# Adafruit_UPDI_Friend.net
KiCad netlist of a schematic drawn in EAGLE
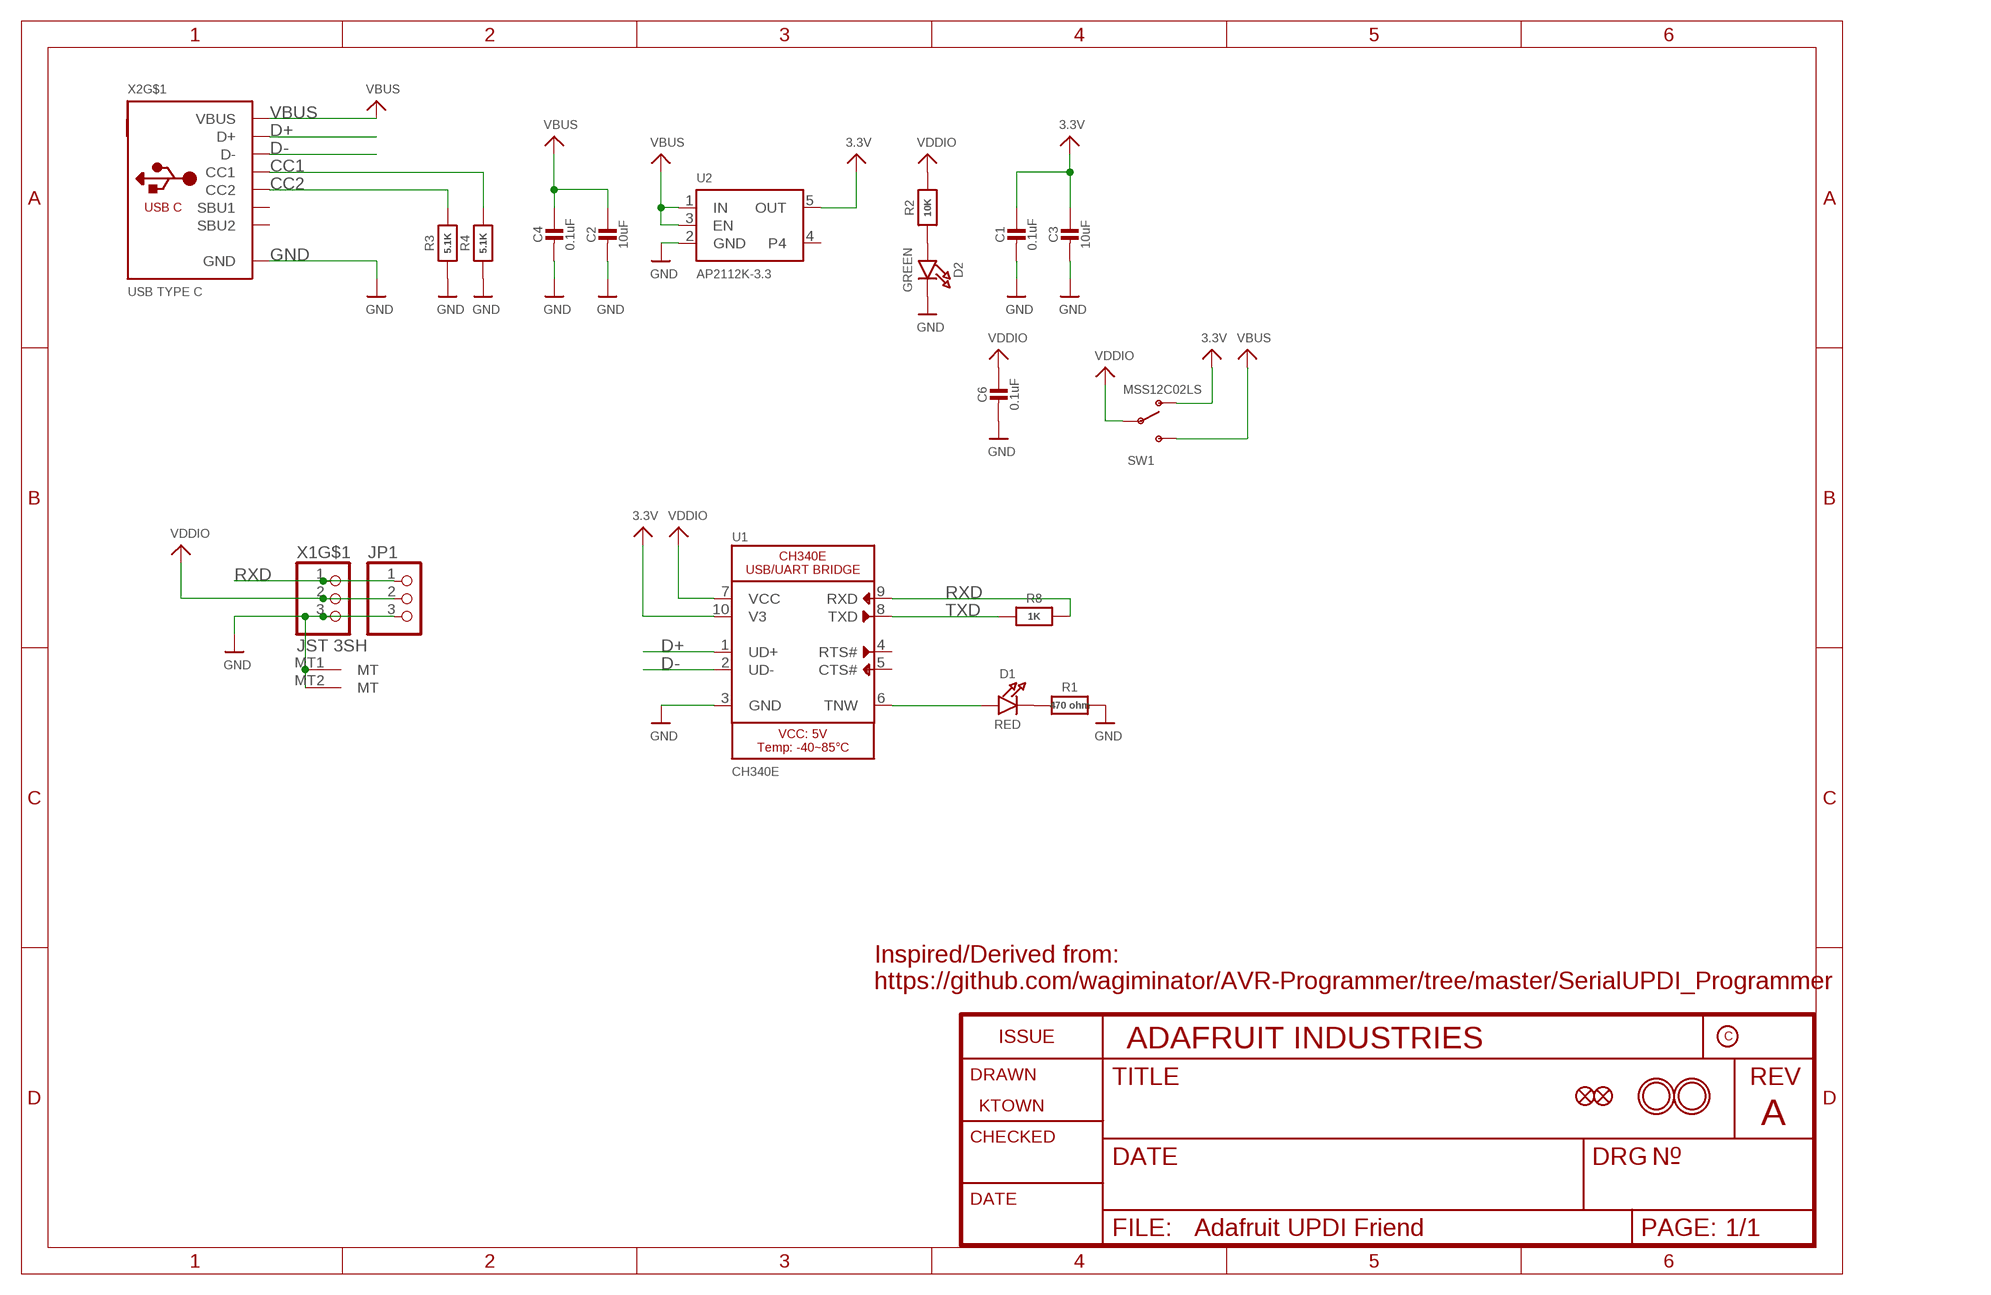
[diagram p0: schematic, sheet 1]

(export (version "E")
  (design (tool "Eeschema 10.0.6"))
  (components
    (comp (ref "C1")
      (value "0.1uF")
      (footprint "eagle-import:0603-NO")
      (libsource (lib "eagle-import") (part "CAP_CERAMIC0603_NO"))
    )
    (comp (ref "C2")
      (value "10uF")
      (footprint "eagle-import:0805-NO")
      (libsource (lib "eagle-import") (part "CAP_CERAMIC0805-NOOUTLINE"))
    )
    (comp (ref "C3")
      (value "10uF")
      (footprint "eagle-import:0805-NO")
      (libsource (lib "eagle-import") (part "CAP_CERAMIC0805-NOOUTLINE"))
    )
    (comp (ref "C4")
      (value "0.1uF")
      (footprint "eagle-import:0603-NO")
      (libsource (lib "eagle-import") (part "CAP_CERAMIC0603_NO"))
    )
    (comp (ref "C6")
      (value "0.1uF")
      (footprint "eagle-import:0603-NO")
      (libsource (lib "eagle-import") (part "CAP_CERAMIC0603_NO"))
    )
    (comp (ref "D1")
      (value "RED")
      (footprint "eagle-import:CHIPLED_0603_NOOUTLINE")
      (libsource (lib "eagle-import") (part "LED0603_NOOUTLINE"))
    )
    (comp (ref "D2")
      (value "GREEN")
      (footprint "eagle-import:CHIPLED_0603_NOOUTLINE")
      (libsource (lib "eagle-import") (part "LED0603_NOOUTLINE"))
    )
    (comp (ref "FID1")
      (value "FIDUCIAL_1MM")
      (footprint "eagle-import:FIDUCIAL_1MM")
      (libsource (lib "eagle-import") (part "FIDUCIAL_1MM"))
    )
    (comp (ref "FID2")
      (value "FIDUCIAL_1MM")
      (footprint "eagle-import:FIDUCIAL_1MM")
      (libsource (lib "eagle-import") (part "FIDUCIAL_1MM"))
    )
    (comp (ref "JP1")
      (value "HEADER-1X376MIL")
      (footprint "eagle-import:1X03_ROUND_76")
      (libsource (lib "eagle-import") (part "HEADER-1X376MIL"))
    )
    (comp (ref "R1")
      (value "470 ohm")
      (footprint "eagle-import:0603-NO")
      (libsource (lib "eagle-import") (part "RESISTOR_0603_NOOUT"))
    )
    (comp (ref "R2")
      (value "10K")
      (footprint "eagle-import:0603-NO")
      (libsource (lib "eagle-import") (part "RESISTOR_0603_NOOUT"))
    )
    (comp (ref "R3")
      (value "5.1K")
      (footprint "eagle-import:0603-NO")
      (libsource (lib "eagle-import") (part "RESISTOR_0603_NOOUT"))
    )
    (comp (ref "R4")
      (value "5.1K")
      (footprint "eagle-import:0603-NO")
      (libsource (lib "eagle-import") (part "RESISTOR_0603_NOOUT"))
    )
    (comp (ref "R8")
      (value "1K")
      (footprint "eagle-import:0603-NO")
      (libsource (lib "eagle-import") (part "RESISTOR_0603_NOOUT"))
    )
    (comp (ref "SW1")
      (value "MSS12C02LS")
      (footprint "eagle-import:SPDT_SMT_SSSS811101")
      (libsource (lib "eagle-import") (part "SWITCH_SPDT"))
    )
    (comp (ref "U$18")
      (value "MOUNTINGHOLE2.0")
      (footprint "eagle-import:MOUNTINGHOLE_2.0_PLATED")
      (libsource (lib "eagle-import") (part "MOUNTINGHOLE2.0"))
    )
    (comp (ref "U$19")
      (value "MOUNTINGHOLE2.0")
      (footprint "eagle-import:MOUNTINGHOLE_2.0_PLATED")
      (libsource (lib "eagle-import") (part "MOUNTINGHOLE2.0"))
    )
    (comp (ref "U1")
      (value "CH340E")
      (footprint "eagle-import:MSOP10")
      (libsource (lib "eagle-import") (part "CH340E_MSOP10"))
    )
    (comp (ref "U2")
      (value "AP2112K-3.3")
      (footprint "eagle-import:SOT23-5")
      (fields (field (name "JLC_ROTATION") "0"))
      (libsource (lib "eagle-import") (part "VREG_SOT23-5"))
    )
    (comp (ref "X1")
      (value "JST 3SH")
      (footprint "eagle-import:JST_SH3")
      (libsource (lib "eagle-import") (part "CON_JST_SH_3PINHORZ"))
    )
    (comp (ref "X2")
      (value "USB TYPE C")
      (footprint "eagle-import:USB_C_CUSB31-CFM2AX-01-X")
      (libsource (lib "eagle-import") (part "USB_C"))
    )
  )
  (nets
    (net (code "1") (name "/CC1") (class "Default")
      (node (ref "R4") (pin "2") (pinfunction "2_2") (pintype "passive"))
      (node (ref "X2") (pin "A5") (pinfunction "CC1_A5") (pintype "bidirectional"))
    )
    (net (code "2") (name "/CC2") (class "Default")
      (node (ref "R3") (pin "2") (pinfunction "2_2") (pintype "passive"))
      (node (ref "X2") (pin "B5") (pinfunction "CC2_B5") (pintype "bidirectional"))
    )
    (net (code "3") (name "/D+") (class "Default")
      (node (ref "U1") (pin "1") (pinfunction "UD+_1") (pintype "bidirectional"))
      (node (ref "X2") (pin "A6") (pinfunction "D+_A6") (pintype "bidirectional"))
      (node (ref "X2") (pin "B6") (pinfunction "D+_B6") (pintype "bidirectional"))
    )
    (net (code "4") (name "/D-") (class "Default")
      (node (ref "U1") (pin "2") (pinfunction "UD-_2") (pintype "bidirectional"))
      (node (ref "X2") (pin "A7") (pinfunction "D-_A7") (pintype "bidirectional"))
      (node (ref "X2") (pin "B7") (pinfunction "D-_B7") (pintype "bidirectional"))
    )
    (net (code "5") (name "/RXD") (class "Default")
      (node (ref "JP1") (pin "1") (pinfunction "1_1") (pintype "passive"))
      (node (ref "R8") (pin "2") (pinfunction "2_2") (pintype "passive"))
      (node (ref "U1") (pin "9") (pinfunction "RXD_9") (pintype "input"))
      (node (ref "X1") (pin "1") (pinfunction "1_1") (pintype "passive"))
    )
    (net (code "6") (name "/TXD") (class "Default")
      (node (ref "R8") (pin "1") (pinfunction "1_1") (pintype "passive"))
      (node (ref "U1") (pin "8") (pinfunction "TXD_8") (pintype "output"))
    )
    (net (code "7") (name "3.3V") (class "Default")
      (node (ref "C1") (pin "1") (pinfunction "1_1") (pintype "passive"))
      (node (ref "C3") (pin "1") (pinfunction "1_1") (pintype "passive"))
      (node (ref "SW1") (pin "A") (pinfunction "O_A") (pintype "passive"))
      (node (ref "U1") (pin "10") (pinfunction "V3_10") (pintype "bidirectional"))
      (node (ref "U2") (pin "5") (pinfunction "OUT_5") (pintype "power_in"))
    )
    (net (code "8") (name "GND") (class "Default")
      (node (ref "C1") (pin "2") (pinfunction "2_2") (pintype "passive"))
      (node (ref "C2") (pin "2") (pinfunction "2_2") (pintype "passive"))
      (node (ref "C3") (pin "2") (pinfunction "2_2") (pintype "passive"))
      (node (ref "C4") (pin "2") (pinfunction "2_2") (pintype "passive"))
      (node (ref "C6") (pin "2") (pinfunction "2_2") (pintype "passive"))
      (node (ref "D2") (pin "C") (pinfunction "C_C") (pintype "passive"))
      (node (ref "JP1") (pin "3") (pinfunction "3_3") (pintype "passive"))
      (node (ref "R1") (pin "2") (pinfunction "2_2") (pintype "passive"))
      (node (ref "R3") (pin "1") (pinfunction "1_1") (pintype "passive"))
      (node (ref "R4") (pin "1") (pinfunction "1_1") (pintype "passive"))
      (node (ref "U1") (pin "3") (pinfunction "GND_3") (pintype "power_in"))
      (node (ref "U2") (pin "2") (pinfunction "GND_2") (pintype "power_in"))
      (node (ref "X1") (pin "3") (pinfunction "3_3") (pintype "passive"))
      (node (ref "X1") (pin "MT1") (pinfunction "MT_MT1") (pintype "bidirectional"))
      (node (ref "X1") (pin "MT2") (pinfunction "MT_MT2") (pintype "bidirectional"))
      (node (ref "X2") (pin "A1B12") (pinfunction "GND_A1B12") (pintype "power_in"))
      (node (ref "X2") (pin "B1A12") (pinfunction "GND_B1A12") (pintype "power_in"))
    )
    (net (code "9") (name "Net-(D1-PadC)") (class "Default")
      (node (ref "D1") (pin "C") (pinfunction "C_C") (pintype "passive"))
      (node (ref "R1") (pin "1") (pinfunction "1_1") (pintype "passive"))
    )
    (net (code "10") (name "Net-(D2-PadA)") (class "Default")
      (node (ref "D2") (pin "A") (pinfunction "A_A") (pintype "passive"))
      (node (ref "R2") (pin "1") (pinfunction "1_1") (pintype "passive"))
    )
    (net (code "11") (name "Net-(U1-TNW)") (class "Default")
      (node (ref "D1") (pin "A") (pinfunction "A_A") (pintype "passive"))
      (node (ref "U1") (pin "6") (pinfunction "TNW_6") (pintype "output"))
    )
    (net (code "12") (name "VBUS") (class "Default")
      (node (ref "C2") (pin "1") (pinfunction "1_1") (pintype "passive"))
      (node (ref "C4") (pin "1") (pinfunction "1_1") (pintype "passive"))
      (node (ref "SW1") (pin "C") (pinfunction "S_C") (pintype "passive"))
      (node (ref "U2") (pin "1") (pinfunction "IN_1") (pintype "power_in"))
      (node (ref "U2") (pin "3") (pinfunction "EN_3") (pintype "input"))
      (node (ref "X2") (pin "A4B9") (pinfunction "VBUS_A4B9") (pintype "power_in"))
      (node (ref "X2") (pin "B4A9") (pinfunction "VBUS_B4A9") (pintype "power_in"))
    )
    (net (code "13") (name "VDDIO") (class "Default")
      (node (ref "C6") (pin "1") (pinfunction "1_1") (pintype "passive"))
      (node (ref "JP1") (pin "2") (pinfunction "2_2") (pintype "passive"))
      (node (ref "R2") (pin "2") (pinfunction "2_2") (pintype "passive"))
      (node (ref "SW1") (pin "B") (pinfunction "P_B") (pintype "passive"))
      (node (ref "U1") (pin "7") (pinfunction "VCC_7") (pintype "power_in"))
      (node (ref "X1") (pin "2") (pinfunction "2_2") (pintype "passive"))
    )
    (net (code "14") (name "unconnected-(U1-CTS#-Pad5)") (class "Default")
      (node (ref "U1") (pin "5") (pinfunction "CTS#_5") (pintype "input"))
    )
    (net (code "15") (name "unconnected-(U1-RTS#-Pad4)") (class "Default")
      (node (ref "U1") (pin "4") (pinfunction "RTS#_4") (pintype "output"))
    )
    (net (code "16") (name "unconnected-(U2-P4-Pad4)") (class "Default")
      (node (ref "U2") (pin "4") (pinfunction "P4_4") (pintype "bidirectional"))
    )
    (net (code "17") (name "unconnected-(X2A-SBU1-PadA8)") (class "Default")
      (node (ref "X2") (pin "A8") (pinfunction "SBU1_A8") (pintype "bidirectional"))
    )
    (net (code "18") (name "unconnected-(X2A-SBU2-PadB8)") (class "Default")
      (node (ref "X2") (pin "B8") (pinfunction "SBU2_B8") (pintype "bidirectional"))
    )
  )
)
